# GucciAux.net
KiCad netlist of a schematic drawn in EAGLE
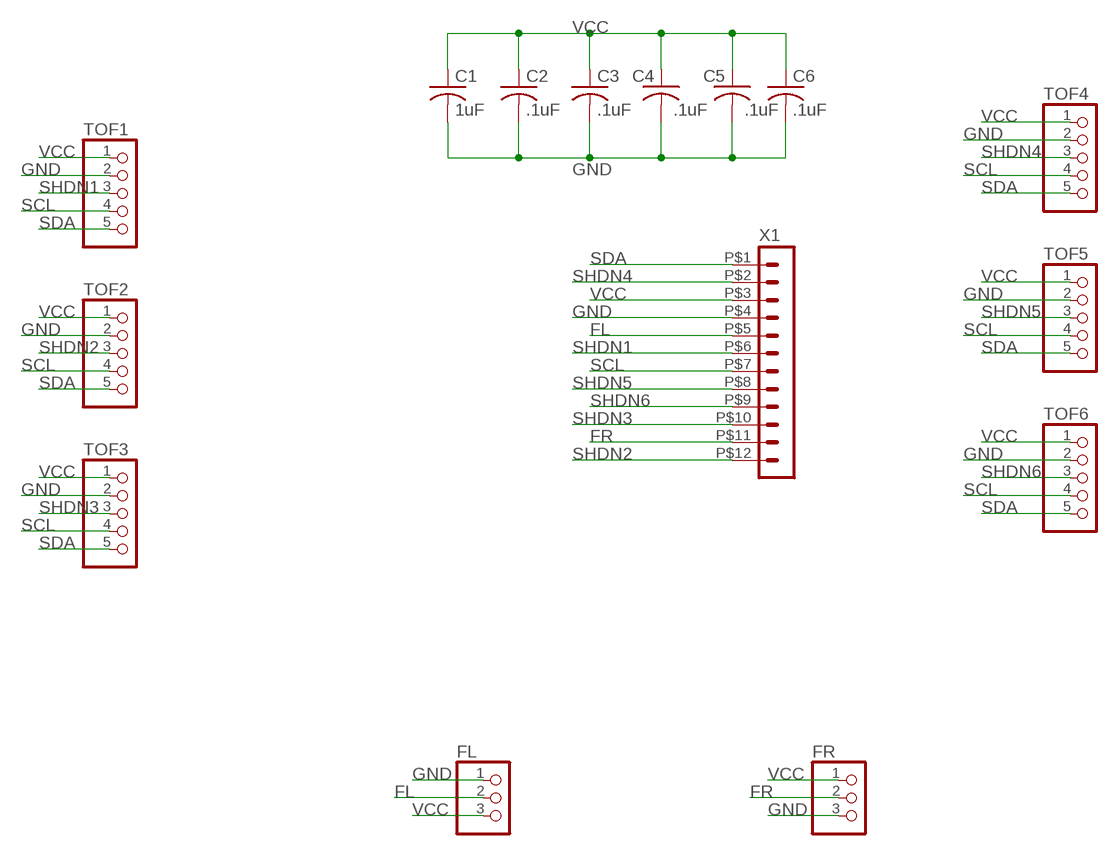
[diagram p0: schematic, sheet 1]

(export (version "E")
  (design (tool "Eeschema 10.0.6"))
  (components
    (comp (ref "C1")
      (value "1uF")
      (footprint "eagle-import:C0402")
      (libsource (lib "eagle-import") (part "C-USC0402"))
    )
    (comp (ref "C2")
      (value ".1uF")
      (footprint "eagle-import:C0402")
      (libsource (lib "eagle-import") (part "C-USC0402"))
    )
    (comp (ref "C3")
      (value ".1uF")
      (footprint "eagle-import:C0402")
      (libsource (lib "eagle-import") (part "C-USC0402"))
    )
    (comp (ref "C4")
      (value ".1uF")
      (footprint "eagle-import:C0402")
      (libsource (lib "eagle-import") (part "C-USC0402"))
    )
    (comp (ref "C5")
      (value ".1uF")
      (footprint "eagle-import:C0402")
      (libsource (lib "eagle-import") (part "C-USC0402"))
    )
    (comp (ref "C6")
      (value ".1uF")
      (footprint "eagle-import:C0402")
      (libsource (lib "eagle-import") (part "C-USC0402"))
    )
    (comp (ref "FL")
      (value "PINHD-1X3")
      (footprint "eagle-import:1X03")
      (libsource (lib "eagle-import") (part "PINHD-1X3"))
    )
    (comp (ref "FR")
      (value "PINHD-1X3")
      (footprint "eagle-import:1X03")
      (libsource (lib "eagle-import") (part "PINHD-1X3"))
    )
    (comp (ref "TOF1")
      (value "PINHD-1X5")
      (footprint "eagle-import:1X05")
      (libsource (lib "eagle-import") (part "PINHD-1X5"))
    )
    (comp (ref "TOF2")
      (value "PINHD-1X5")
      (footprint "eagle-import:1X05")
      (libsource (lib "eagle-import") (part "PINHD-1X5"))
    )
    (comp (ref "TOF3")
      (value "PINHD-1X5")
      (footprint "eagle-import:1X05")
      (libsource (lib "eagle-import") (part "PINHD-1X5"))
    )
    (comp (ref "TOF4")
      (value "PINHD-1X5")
      (footprint "eagle-import:1X05")
      (libsource (lib "eagle-import") (part "PINHD-1X5"))
    )
    (comp (ref "TOF5")
      (value "PINHD-1X5")
      (footprint "eagle-import:1X05")
      (libsource (lib "eagle-import") (part "PINHD-1X5"))
    )
    (comp (ref "TOF6")
      (value "PINHD-1X5")
      (footprint "eagle-import:1X05")
      (libsource (lib "eagle-import") (part "PINHD-1X5"))
    )
    (comp (ref "X1")
      (value "HEADER_POS12_43045-1212")
      (footprint "eagle-import:43045-1212")
      (libsource (lib "eagle-import") (part "HEADER_POS12_?43045-1212"))
    )
  )
  (nets
    (net (code "1") (name "/FL") (class "Default")
      (node (ref "FL") (pin "2") (pinfunction "2_2") (pintype "passive"))
      (node (ref "X1") (pin "P$5") (pinfunction "5_P$5") (pintype "passive"))
    )
    (net (code "2") (name "/FR") (class "Default")
      (node (ref "FR") (pin "2") (pinfunction "2_2") (pintype "passive"))
      (node (ref "X1") (pin "P$11") (pinfunction "11_P$11") (pintype "passive"))
    )
    (net (code "3") (name "/GND") (class "Default")
      (node (ref "C1") (pin "2") (pinfunction "2_2") (pintype "passive"))
      (node (ref "C2") (pin "2") (pinfunction "2_2") (pintype "passive"))
      (node (ref "C3") (pin "2") (pinfunction "2_2") (pintype "passive"))
      (node (ref "C4") (pin "2") (pinfunction "2_2") (pintype "passive"))
      (node (ref "C5") (pin "2") (pinfunction "2_2") (pintype "passive"))
      (node (ref "C6") (pin "2") (pinfunction "2_2") (pintype "passive"))
      (node (ref "FL") (pin "1") (pinfunction "1_1") (pintype "passive"))
      (node (ref "FR") (pin "3") (pinfunction "3_3") (pintype "passive"))
      (node (ref "TOF1") (pin "2") (pinfunction "2_2") (pintype "passive"))
      (node (ref "TOF2") (pin "2") (pinfunction "2_2") (pintype "passive"))
      (node (ref "TOF3") (pin "2") (pinfunction "2_2") (pintype "passive"))
      (node (ref "TOF4") (pin "2") (pinfunction "2_2") (pintype "passive"))
      (node (ref "TOF5") (pin "2") (pinfunction "2_2") (pintype "passive"))
      (node (ref "TOF6") (pin "2") (pinfunction "2_2") (pintype "passive"))
      (node (ref "X1") (pin "P$4") (pinfunction "4_P$4") (pintype "passive"))
    )
    (net (code "4") (name "/SCL") (class "Default")
      (node (ref "TOF1") (pin "4") (pinfunction "4_4") (pintype "passive"))
      (node (ref "TOF2") (pin "4") (pinfunction "4_4") (pintype "passive"))
      (node (ref "TOF3") (pin "4") (pinfunction "4_4") (pintype "passive"))
      (node (ref "TOF4") (pin "4") (pinfunction "4_4") (pintype "passive"))
      (node (ref "TOF5") (pin "4") (pinfunction "4_4") (pintype "passive"))
      (node (ref "TOF6") (pin "4") (pinfunction "4_4") (pintype "passive"))
      (node (ref "X1") (pin "P$7") (pinfunction "7_P$7") (pintype "passive"))
    )
    (net (code "5") (name "/SDA") (class "Default")
      (node (ref "TOF1") (pin "5") (pinfunction "5_5") (pintype "passive"))
      (node (ref "TOF2") (pin "5") (pinfunction "5_5") (pintype "passive"))
      (node (ref "TOF3") (pin "5") (pinfunction "5_5") (pintype "passive"))
      (node (ref "TOF4") (pin "5") (pinfunction "5_5") (pintype "passive"))
      (node (ref "TOF5") (pin "5") (pinfunction "5_5") (pintype "passive"))
      (node (ref "TOF6") (pin "5") (pinfunction "5_5") (pintype "passive"))
      (node (ref "X1") (pin "P$1") (pinfunction "1_P$1") (pintype "passive"))
    )
    (net (code "6") (name "/SHDN1") (class "Default")
      (node (ref "TOF1") (pin "3") (pinfunction "3_3") (pintype "passive"))
      (node (ref "X1") (pin "P$6") (pinfunction "6_P$6") (pintype "passive"))
    )
    (net (code "7") (name "/SHDN2") (class "Default")
      (node (ref "TOF2") (pin "3") (pinfunction "3_3") (pintype "passive"))
      (node (ref "X1") (pin "P$12") (pinfunction "12_P$12") (pintype "passive"))
    )
    (net (code "8") (name "/SHDN3") (class "Default")
      (node (ref "TOF3") (pin "3") (pinfunction "3_3") (pintype "passive"))
      (node (ref "X1") (pin "P$10") (pinfunction "10_P$10") (pintype "passive"))
    )
    (net (code "9") (name "/SHDN4") (class "Default")
      (node (ref "TOF4") (pin "3") (pinfunction "3_3") (pintype "passive"))
      (node (ref "X1") (pin "P$2") (pinfunction "2_P$2") (pintype "passive"))
    )
    (net (code "10") (name "/SHDN5") (class "Default")
      (node (ref "TOF5") (pin "3") (pinfunction "3_3") (pintype "passive"))
      (node (ref "X1") (pin "P$8") (pinfunction "8_P$8") (pintype "passive"))
    )
    (net (code "11") (name "/SHDN6") (class "Default")
      (node (ref "TOF6") (pin "3") (pinfunction "3_3") (pintype "passive"))
      (node (ref "X1") (pin "P$9") (pinfunction "9_P$9") (pintype "passive"))
    )
    (net (code "12") (name "/VCC") (class "Default")
      (node (ref "C1") (pin "1") (pinfunction "1_1") (pintype "passive"))
      (node (ref "C2") (pin "1") (pinfunction "1_1") (pintype "passive"))
      (node (ref "C3") (pin "1") (pinfunction "1_1") (pintype "passive"))
      (node (ref "C4") (pin "1") (pinfunction "1_1") (pintype "passive"))
      (node (ref "C5") (pin "1") (pinfunction "1_1") (pintype "passive"))
      (node (ref "C6") (pin "1") (pinfunction "1_1") (pintype "passive"))
      (node (ref "FL") (pin "3") (pinfunction "3_3") (pintype "passive"))
      (node (ref "FR") (pin "1") (pinfunction "1_1") (pintype "passive"))
      (node (ref "TOF1") (pin "1") (pinfunction "1_1") (pintype "passive"))
      (node (ref "TOF2") (pin "1") (pinfunction "1_1") (pintype "passive"))
      (node (ref "TOF3") (pin "1") (pinfunction "1_1") (pintype "passive"))
      (node (ref "TOF4") (pin "1") (pinfunction "1_1") (pintype "passive"))
      (node (ref "TOF5") (pin "1") (pinfunction "1_1") (pintype "passive"))
      (node (ref "TOF6") (pin "1") (pinfunction "1_1") (pintype "passive"))
      (node (ref "X1") (pin "P$3") (pinfunction "3_P$3") (pintype "passive"))
    )
  )
)
